# gydrodrive_button.net
KiCad netlist of a schematic drawn in Altium Designer
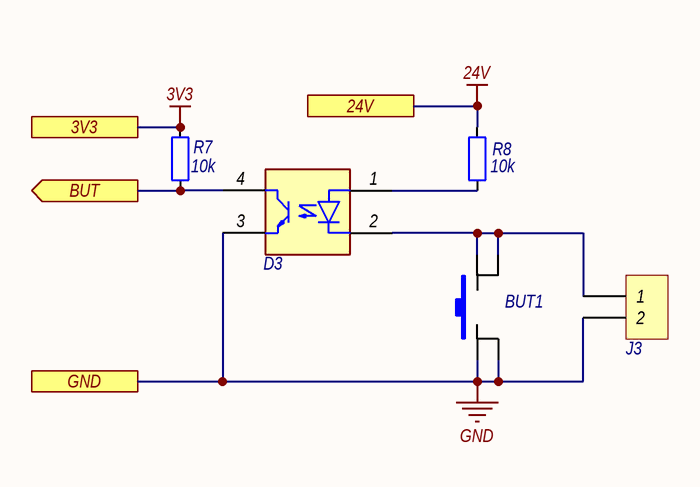
[diagram p0: gydrodrive_button.SchDoc]

(export (version "E")
  (design (tool "Eeschema 10.0.6"))
  (components
    (comp (ref "BUT1")
      (value "KLS7-TS6604-4.3-180")
      (footprint "SWITCH_6x6_SMD")
      (description "Тактовая кнопка SMD")
      (libsource (lib "StdLib") (part "BUTTON"))
    )
    (comp (ref "D3")
      (value "LTV-817S")
      (footprint "DIP-4-SMD")
      (description "Оптопара транзисторная одноканальная")
      (libsource (lib "StdLib") (part "LTV-817"))
    )
    (comp (ref "J3")
      (value "DG142V-5.08-02P")
      (footprint "DG142V-5.08-02P")
      (description "Клеммник 2-контактный, шаг 5.08 мм")
      (libsource (lib "StdLib") (part "PIN1x2"))
    )
    (comp (ref "R7")
      (value "RES_0805")
      (footprint "RESC2012-0805M")
      (description "Рез-р, корпус 0805")
      (fields
        (field (name "RESISTANCE") "10k")
        (field (name "PART NUMBER") "RESC_0805")
        (field (name "TOLERANCE") "5%")
      )
      (libsource (lib "StdLib") (part "RES"))
    )
    (comp (ref "R8")
      (value "RES_0805")
      (footprint "RESC2012-0805M")
      (description "Рез-р, корпус 0805")
      (fields
        (field (name "RESISTANCE") "10k")
        (field (name "PART NUMBER") "RESC_0805")
        (field (name "TOLERANCE") "5%")
      )
      (libsource (lib "StdLib") (part "RES"))
    )
  )
  (nets
    (net (code "1") (name "/BUT") (class "Default")
      (node (ref "D3") (pin "4") (pinfunction "A_4") (pintype "passive"))
      (node (ref "R7") (pin "1") (pinfunction "1_1") (pintype "passive"))
    )
    (net (code "2") (name "3V3") (class "Default")
      (node (ref "R7") (pin "2") (pinfunction "2_2") (pintype "passive"))
    )
    (net (code "3") (name "24V") (class "Default")
      (node (ref "R8") (pin "2") (pinfunction "2_2") (pintype "passive"))
    )
    (net (code "4") (name "GND") (class "Default")
      (node (ref "BUT1") (pin "3") (pinfunction "3_3") (pintype "passive"))
      (node (ref "BUT1") (pin "4") (pinfunction "4_4") (pintype "passive"))
      (node (ref "D3") (pin "3") (pinfunction "C_3") (pintype "passive"))
      (node (ref "J3") (pin "2") (pinfunction "2_2") (pintype "passive"))
    )
    (net (code "5") (name "Net-(D3-E)") (class "Default")
      (node (ref "BUT1") (pin "1") (pinfunction "1_1") (pintype "passive"))
      (node (ref "BUT1") (pin "2") (pinfunction "2_2") (pintype "passive"))
      (node (ref "D3") (pin "2") (pinfunction "E_2") (pintype "passive"))
      (node (ref "J3") (pin "1") (pinfunction "1_1") (pintype "passive"))
    )
    (net (code "6") (name "Net-(D3-K)") (class "Default")
      (node (ref "D3") (pin "1") (pinfunction "K_1") (pintype "passive"))
      (node (ref "R8") (pin "1") (pinfunction "1_1") (pintype "passive"))
    )
  )
)
